# Support.net
KiCad netlist of a schematic drawn in Altium Designer
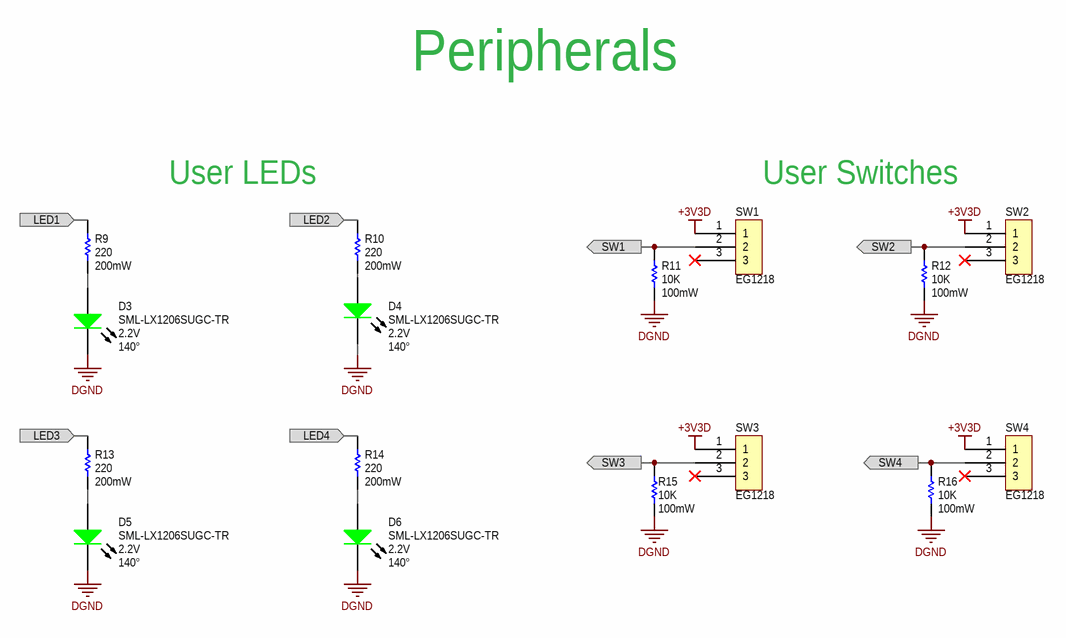
[diagram p0: Support.SchDoc]

(export (version "E")
  (design (tool "Eeschema 10.0.6"))
  (components
    (comp (ref "D3")
      (value "SML-LX1206SUGC-TR")
      (footprint "DIOCP3216X11L")
      (description "LED ALINGAP ULT GRN CLR 1206 SMD")
      (fields
        (field (name "MANUFACTURER") "Lumex Opto/Components Inc")
        (field (name "MANUFACTURER PART NUMBER") "SML-LX1206SUGC-TR")
        (field (name "VOLTAGE - FORWARD (VF) TYP") "2.2V")
        (field (name "VIEWING ANGLE") "140°")
      )
      (libsource (lib "Schematic_Components") (part "LED_GREEN 2"))
    )
    (comp (ref "D4")
      (value "SML-LX1206SUGC-TR")
      (footprint "DIOCP3216X11L")
      (description "LED ALINGAP ULT GRN CLR 1206 SMD")
      (fields
        (field (name "MANUFACTURER") "Lumex Opto/Components Inc")
        (field (name "MANUFACTURER PART NUMBER") "SML-LX1206SUGC-TR")
        (field (name "VOLTAGE - FORWARD (VF) TYP") "2.2V")
        (field (name "VIEWING ANGLE") "140°")
      )
      (libsource (lib "Schematic_Components") (part "LED_GREEN 2"))
    )
    (comp (ref "D5")
      (value "SML-LX1206SUGC-TR")
      (footprint "DIOCP3216X11L")
      (description "LED ALINGAP ULT GRN CLR 1206 SMD")
      (fields
        (field (name "MANUFACTURER") "Lumex Opto/Components Inc")
        (field (name "MANUFACTURER PART NUMBER") "SML-LX1206SUGC-TR")
        (field (name "VOLTAGE - FORWARD (VF) TYP") "2.2V")
        (field (name "VIEWING ANGLE") "140°")
      )
      (libsource (lib "Schematic_Components") (part "LED_GREEN 2"))
    )
    (comp (ref "D6")
      (value "SML-LX1206SUGC-TR")
      (footprint "DIOCP3216X11L")
      (description "LED ALINGAP ULT GRN CLR 1206 SMD")
      (fields
        (field (name "MANUFACTURER") "Lumex Opto/Components Inc")
        (field (name "MANUFACTURER PART NUMBER") "SML-LX1206SUGC-TR")
        (field (name "VOLTAGE - FORWARD (VF) TYP") "2.2V")
        (field (name "VIEWING ANGLE") "140°")
      )
      (libsource (lib "Schematic_Components") (part "LED_GREEN 2"))
    )
    (comp (ref "R9")
      (value "ERJ-PB3B2200V")
      (footprint "3-0603_R_L")
      (description "RES SMD 220 OHM 0.1% 1/5W 0603")
      (fields
        (field (name "MANUFACTURER") "Panasonic Electronic Components")
        (field (name "TOLERANCE") "±0.1%")
        (field (name "POWER (WATTS)") "200mW")
        (field (name "RESISTANCE (OHMS)") "220")
      )
      (libsource (lib "Schematic_Components_CD") (part "ERJ-PB3B2200V"))
    )
    (comp (ref "R10")
      (value "ERJ-PB3B2200V")
      (footprint "3-0603_R_L")
      (description "RES SMD 220 OHM 0.1% 1/5W 0603")
      (fields
        (field (name "MANUFACTURER") "Panasonic Electronic Components")
        (field (name "TOLERANCE") "±0.1%")
        (field (name "POWER (WATTS)") "200mW")
        (field (name "RESISTANCE (OHMS)") "220")
      )
      (libsource (lib "Schematic_Components_CD") (part "ERJ-PB3B2200V"))
    )
    (comp (ref "R11")
      (value "ERJ-3GEYJ103V")
      (footprint "3-0603_R_L")
      (description "RES 10K OHM 1/10W 5% 0603 SMD")
      (fields
        (field (name "MANUFACTURER") "Panasonic - ECG")
        (field (name "POWER (WATTS)") "100mW")
        (field (name "TOLERANCE") "±5%")
        (field (name "RESISTANCE (OHMS)") "10K")
      )
      (libsource (lib "Schematic_Components") (part "ERJ-3GEYJ103V"))
    )
    (comp (ref "R12")
      (value "ERJ-3GEYJ103V")
      (footprint "3-0603_R_L")
      (description "RES 10K OHM 1/10W 5% 0603 SMD")
      (fields
        (field (name "MANUFACTURER") "Panasonic - ECG")
        (field (name "POWER (WATTS)") "100mW")
        (field (name "TOLERANCE") "±5%")
        (field (name "RESISTANCE (OHMS)") "10K")
      )
      (libsource (lib "Schematic_Components") (part "ERJ-3GEYJ103V"))
    )
    (comp (ref "R13")
      (value "ERJ-PB3B2200V")
      (footprint "3-0603_R_L")
      (description "RES SMD 220 OHM 0.1% 1/5W 0603")
      (fields
        (field (name "MANUFACTURER") "Panasonic Electronic Components")
        (field (name "TOLERANCE") "±0.1%")
        (field (name "POWER (WATTS)") "200mW")
        (field (name "RESISTANCE (OHMS)") "220")
      )
      (libsource (lib "Schematic_Components_CD") (part "ERJ-PB3B2200V"))
    )
    (comp (ref "R14")
      (value "ERJ-PB3B2200V")
      (footprint "3-0603_R_L")
      (description "RES SMD 220 OHM 0.1% 1/5W 0603")
      (fields
        (field (name "MANUFACTURER") "Panasonic Electronic Components")
        (field (name "TOLERANCE") "±0.1%")
        (field (name "POWER (WATTS)") "200mW")
        (field (name "RESISTANCE (OHMS)") "220")
      )
      (libsource (lib "Schematic_Components_CD") (part "ERJ-PB3B2200V"))
    )
    (comp (ref "R15")
      (value "ERJ-3GEYJ103V")
      (footprint "3-0603_R_L")
      (description "RES 10K OHM 1/10W 5% 0603 SMD")
      (fields
        (field (name "MANUFACTURER") "Panasonic - ECG")
        (field (name "POWER (WATTS)") "100mW")
        (field (name "TOLERANCE") "±5%")
        (field (name "RESISTANCE (OHMS)") "10K")
      )
      (libsource (lib "Schematic_Components") (part "ERJ-3GEYJ103V"))
    )
    (comp (ref "R16")
      (value "ERJ-3GEYJ103V")
      (footprint "3-0603_R_L")
      (description "RES 10K OHM 1/10W 5% 0603 SMD")
      (fields
        (field (name "MANUFACTURER") "Panasonic - ECG")
        (field (name "POWER (WATTS)") "100mW")
        (field (name "TOLERANCE") "±5%")
        (field (name "RESISTANCE (OHMS)") "10K")
      )
      (libsource (lib "Schematic_Components") (part "ERJ-3GEYJ103V"))
    )
    (comp (ref "SW1")
      (value "EG1218")
      (footprint "EG1218")
      (description "Slide Switch SPDT Through Hole")
      (fields
        (field (name "MANUFACTURER") "E-Switch")
        (field (name "MANUFACTURER PART NUMBER") "EG1218")
        (field (name "PUBLISHER") "Altium Limited")
      )
      (libsource (lib "NIH_DE0_Nano_Daughter_Card_Library") (part "EG1218"))
    )
    (comp (ref "SW2")
      (value "EG1218")
      (footprint "EG1218")
      (description "Slide Switch SPDT Through Hole")
      (fields
        (field (name "MANUFACTURER") "E-Switch")
        (field (name "MANUFACTURER PART NUMBER") "EG1218")
        (field (name "PUBLISHER") "Altium Limited")
      )
      (libsource (lib "NIH_DE0_Nano_Daughter_Card_Library") (part "EG1218"))
    )
    (comp (ref "SW3")
      (value "EG1218")
      (footprint "EG1218")
      (description "Slide Switch SPDT Through Hole")
      (fields
        (field (name "MANUFACTURER") "E-Switch")
        (field (name "MANUFACTURER PART NUMBER") "EG1218")
        (field (name "PUBLISHER") "Altium Limited")
      )
      (libsource (lib "NIH_DE0_Nano_Daughter_Card_Library") (part "EG1218"))
    )
    (comp (ref "SW4")
      (value "EG1218")
      (footprint "EG1218")
      (description "Slide Switch SPDT Through Hole")
      (fields
        (field (name "MANUFACTURER") "E-Switch")
        (field (name "MANUFACTURER PART NUMBER") "EG1218")
        (field (name "PUBLISHER") "Altium Limited")
      )
      (libsource (lib "NIH_DE0_Nano_Daughter_Card_Library") (part "EG1218"))
    )
  )
  (nets
    (net (code "1") (name "+3V3D") (class "Default")
      (node (ref "SW1") (pin "1") (pinfunction "1_1") (pintype "passive"))
      (node (ref "SW2") (pin "1") (pinfunction "1_1") (pintype "passive"))
      (node (ref "SW3") (pin "1") (pinfunction "1_1") (pintype "passive"))
      (node (ref "SW4") (pin "1") (pinfunction "1_1") (pintype "passive"))
    )
    (net (code "2") (name "/LED1") (class "Default")
      (node (ref "R9") (pin "2") (pinfunction "2_2") (pintype "passive"))
    )
    (net (code "3") (name "/LED2") (class "Default")
      (node (ref "R10") (pin "2") (pinfunction "2_2") (pintype "passive"))
    )
    (net (code "4") (name "/LED3") (class "Default")
      (node (ref "R13") (pin "2") (pinfunction "2_2") (pintype "passive"))
    )
    (net (code "5") (name "/LED4") (class "Default")
      (node (ref "R14") (pin "2") (pinfunction "2_2") (pintype "passive"))
    )
    (net (code "6") (name "/SW1") (class "Default")
      (node (ref "R11") (pin "1") (pinfunction "1_1") (pintype "passive"))
      (node (ref "SW1") (pin "2") (pinfunction "2_2") (pintype "passive"))
    )
    (net (code "7") (name "/SW2") (class "Default")
      (node (ref "R12") (pin "1") (pinfunction "1_1") (pintype "passive"))
      (node (ref "SW2") (pin "2") (pinfunction "2_2") (pintype "passive"))
    )
    (net (code "8") (name "/SW3") (class "Default")
      (node (ref "R15") (pin "1") (pinfunction "1_1") (pintype "passive"))
      (node (ref "SW3") (pin "2") (pinfunction "2_2") (pintype "passive"))
    )
    (net (code "9") (name "/SW4") (class "Default")
      (node (ref "R16") (pin "1") (pinfunction "1_1") (pintype "passive"))
      (node (ref "SW4") (pin "2") (pinfunction "2_2") (pintype "passive"))
    )
    (net (code "10") (name "DGND") (class "Default")
      (node (ref "D3") (pin "2") (pinfunction "K_2") (pintype "passive"))
      (node (ref "D4") (pin "2") (pinfunction "K_2") (pintype "passive"))
      (node (ref "D5") (pin "2") (pinfunction "K_2") (pintype "passive"))
      (node (ref "D6") (pin "2") (pinfunction "K_2") (pintype "passive"))
      (node (ref "R11") (pin "2") (pinfunction "2_2") (pintype "passive"))
      (node (ref "R12") (pin "2") (pinfunction "2_2") (pintype "passive"))
      (node (ref "R15") (pin "2") (pinfunction "2_2") (pintype "passive"))
      (node (ref "R16") (pin "2") (pinfunction "2_2") (pintype "passive"))
    )
    (net (code "11") (name "Net-(D3-A)") (class "Default")
      (node (ref "D3") (pin "1") (pinfunction "A_1") (pintype "passive"))
      (node (ref "R9") (pin "1") (pinfunction "1_1") (pintype "passive"))
    )
    (net (code "12") (name "Net-(D4-A)") (class "Default")
      (node (ref "D4") (pin "1") (pinfunction "A_1") (pintype "passive"))
      (node (ref "R10") (pin "1") (pinfunction "1_1") (pintype "passive"))
    )
    (net (code "13") (name "Net-(D5-A)") (class "Default")
      (node (ref "D5") (pin "1") (pinfunction "A_1") (pintype "passive"))
      (node (ref "R13") (pin "1") (pinfunction "1_1") (pintype "passive"))
    )
    (net (code "14") (name "Net-(D6-A)") (class "Default")
      (node (ref "D6") (pin "1") (pinfunction "A_1") (pintype "passive"))
      (node (ref "R14") (pin "1") (pinfunction "1_1") (pintype "passive"))
    )
    (net (code "15") (name "unconnected-(SW1-Pad3)") (class "Default")
      (node (ref "SW1") (pin "3") (pinfunction "3_3") (pintype "passive+no_connect"))
    )
    (net (code "16") (name "unconnected-(SW2-Pad3)") (class "Default")
      (node (ref "SW2") (pin "3") (pinfunction "3_3") (pintype "passive+no_connect"))
    )
    (net (code "17") (name "unconnected-(SW3-Pad3)") (class "Default")
      (node (ref "SW3") (pin "3") (pinfunction "3_3") (pintype "passive+no_connect"))
    )
    (net (code "18") (name "unconnected-(SW4-Pad3)") (class "Default")
      (node (ref "SW4") (pin "3") (pinfunction "3_3") (pintype "passive+no_connect"))
    )
  )
)
